# Qwiic_AHT20_Breakout.net
KiCad netlist of a schematic drawn in EAGLE
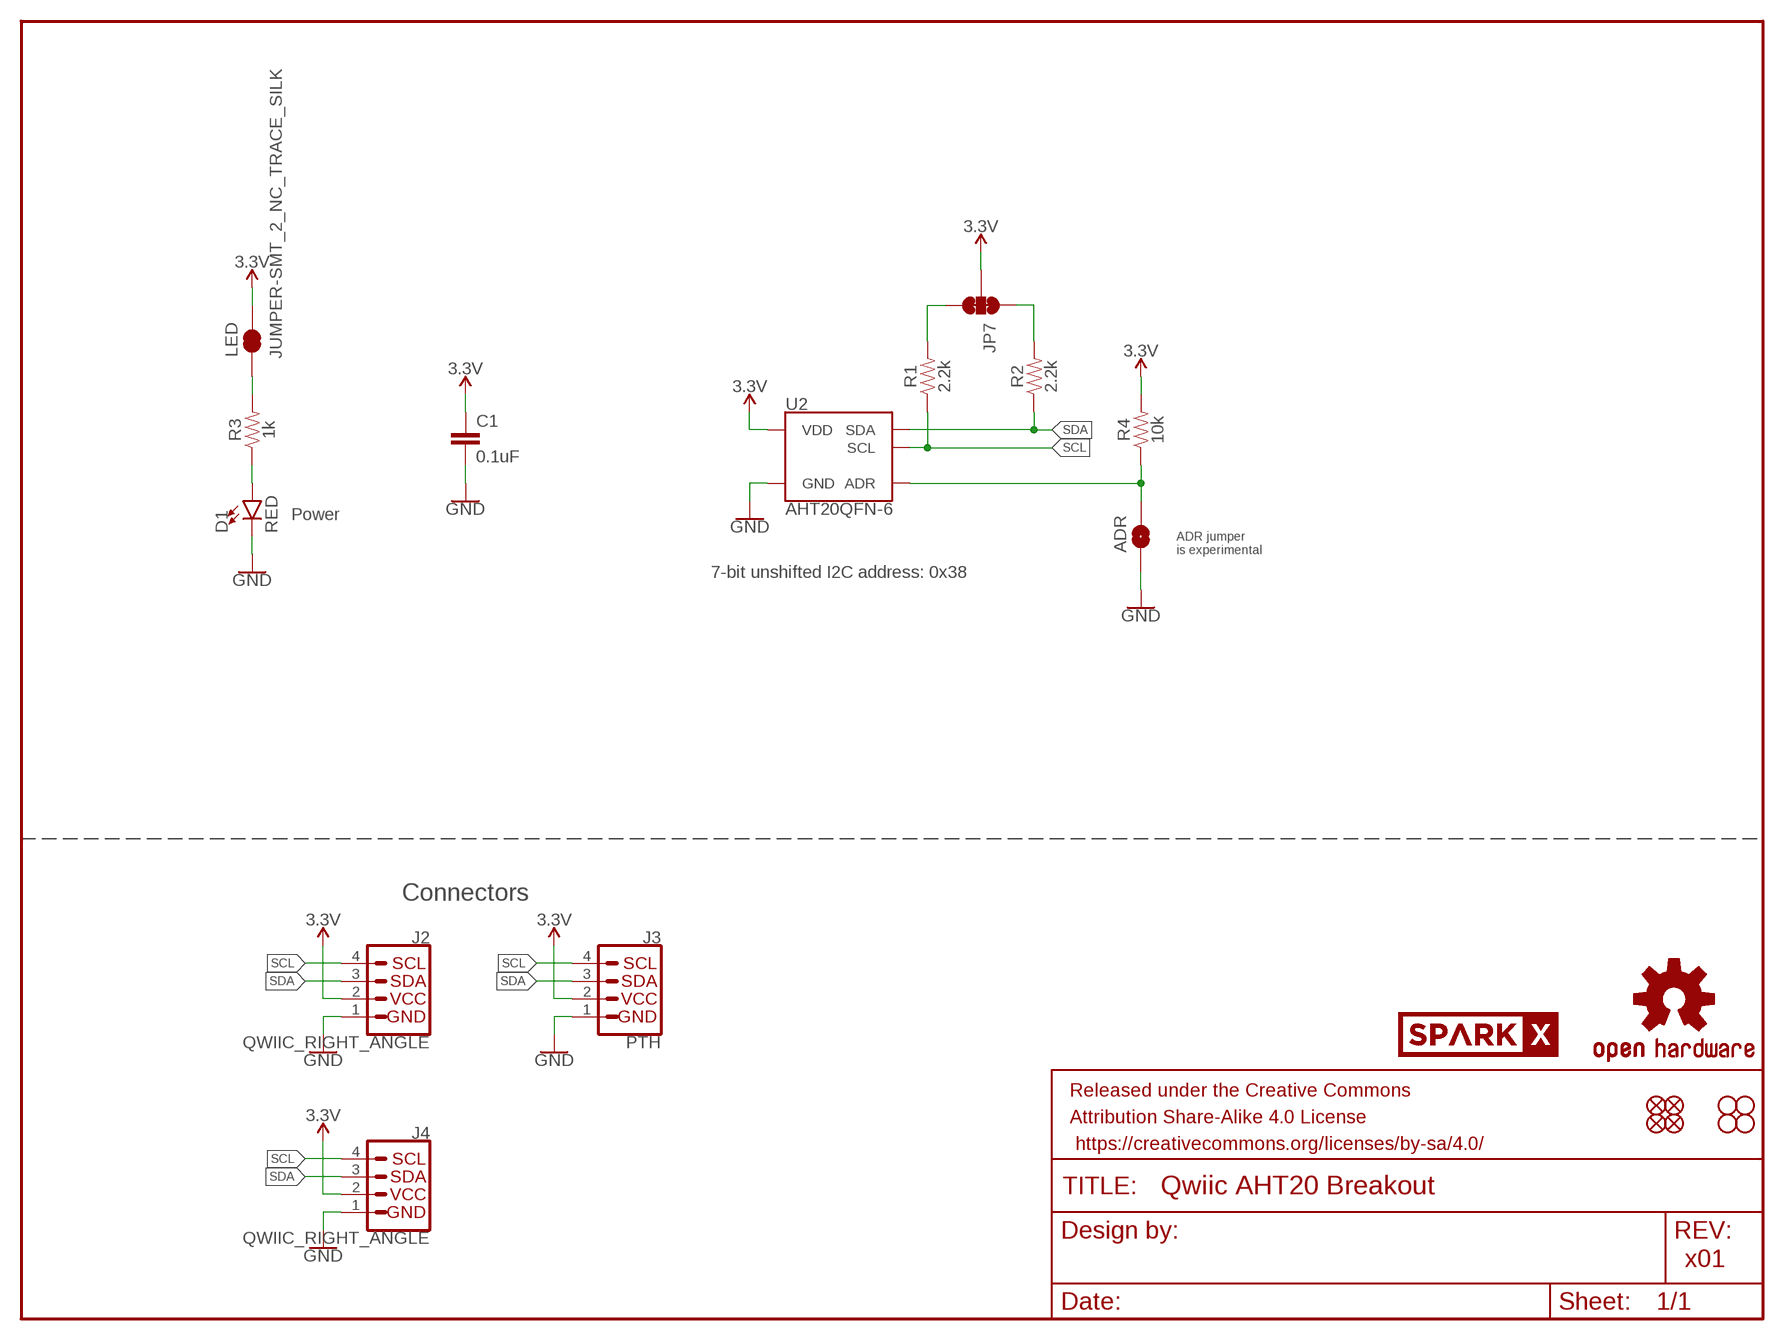
[diagram p0: schematic, sheet 1]

(export (version "E")
  (design (tool "Eeschema 10.0.6"))
  (components
    (comp (ref "ADR")
      (value "JUMPER-SMT_2_NO_SILK")
      (footprint "eagle-import:SMT-JUMPER_2_NO_SILK")
      (libsource (lib "eagle-import") (part "JUMPER-SMT_2_NO_SILK"))
    )
    (comp (ref "C1")
      (value "0.1uF")
      (footprint "eagle-import:0603")
      (libsource (lib "eagle-import") (part "0.1UF-0603-25V-(+80/-20%)"))
    )
    (comp (ref "D1")
      (value "RED")
      (footprint "eagle-import:LED-0603")
      (libsource (lib "eagle-import") (part "LED-RED0603"))
    )
    (comp (ref "FRAME1")
      (value "FRAME-LETTER")
      (footprint "eagle-import:CREATIVE_COMMONS")
      (libsource (lib "eagle-import") (part "FRAME-LETTER"))
    )
    (comp (ref "J2")
      (value "QWIIC_RIGHT_ANGLE")
      (footprint "eagle-import:JST04_1MM_RA")
      (libsource (lib "eagle-import") (part "QWIIC_CONNECTORJS-1MM"))
    )
    (comp (ref "J3")
      (value "PTH")
      (footprint "eagle-import:1X04_NO_SILK")
      (libsource (lib "eagle-import") (part "I2C_STANDARD_NO_SILK"))
    )
    (comp (ref "J4")
      (value "QWIIC_RIGHT_ANGLE")
      (footprint "eagle-import:JST04_1MM_RA")
      (libsource (lib "eagle-import") (part "QWIIC_CONNECTORJS-1MM"))
    )
    (comp (ref "JP1")
      (value "FIDUCIAL1X2")
      (footprint "eagle-import:FIDUCIAL-1X2")
      (libsource (lib "eagle-import") (part "FIDUCIAL1X2"))
    )
    (comp (ref "JP2")
      (value "FIDUCIAL1X2")
      (footprint "eagle-import:FIDUCIAL-1X2")
      (libsource (lib "eagle-import") (part "FIDUCIAL1X2"))
    )
    (comp (ref "JP3")
      (value "STAND-OFF")
      (footprint "eagle-import:STAND-OFF")
      (libsource (lib "eagle-import") (part "STAND-OFF"))
    )
    (comp (ref "JP4")
      (value "STAND-OFF")
      (footprint "eagle-import:STAND-OFF")
      (libsource (lib "eagle-import") (part "STAND-OFF"))
    )
    (comp (ref "JP5")
      (value "FIDUCIAL1X2")
      (footprint "eagle-import:FIDUCIAL-1X2")
      (libsource (lib "eagle-import") (part "FIDUCIAL1X2"))
    )
    (comp (ref "JP6")
      (value "FIDUCIAL1X2")
      (footprint "eagle-import:FIDUCIAL-1X2")
      (libsource (lib "eagle-import") (part "FIDUCIAL1X2"))
    )
    (comp (ref "JP7")
      (value "JUMPER-SMT_3_2-NC_TRACE_SILK")
      (footprint "eagle-import:SMT-JUMPER_3_2-NC_TRACE_SILK")
      (libsource (lib "eagle-import") (part "JUMPER-SMT_3_2-NC_TRACE_SILK"))
    )
    (comp (ref "JP8")
      (value "STAND-OFF")
      (footprint "eagle-import:STAND-OFF")
      (libsource (lib "eagle-import") (part "STAND-OFF"))
    )
    (comp (ref "JP9")
      (value "STAND-OFF")
      (footprint "eagle-import:STAND-OFF")
      (libsource (lib "eagle-import") (part "STAND-OFF"))
    )
    (comp (ref "LED")
      (value "JUMPER-SMT_2_NC_TRACE_SILK")
      (footprint "eagle-import:SMT-JUMPER_2_NC_TRACE_SILK")
      (libsource (lib "eagle-import") (part "JUMPER-SMT_2_NC_TRACE_SILK"))
    )
    (comp (ref "LOGO1")
      (value "OSHW-LOGOMINI")
      (footprint "eagle-import:OSHW-LOGO-MINI")
      (libsource (lib "eagle-import") (part "OSHW-LOGOMINI"))
    )
    (comp (ref "R1")
      (value "2.2k")
      (footprint "eagle-import:0603")
      (libsource (lib "eagle-import") (part "2.2KOHM-0603-1/10W-1%"))
    )
    (comp (ref "R2")
      (value "2.2k")
      (footprint "eagle-import:0603")
      (libsource (lib "eagle-import") (part "2.2KOHM-0603-1/10W-1%"))
    )
    (comp (ref "R3")
      (value "1k")
      (footprint "eagle-import:0603")
      (libsource (lib "eagle-import") (part "1KOHM-0603-1/10W-1%"))
    )
    (comp (ref "R4")
      (value "10k")
      (footprint "eagle-import:0603")
      (libsource (lib "eagle-import") (part "10KOHM-0603-1/10W-1%"))
    )
    (comp (ref "U$1")
      (value "SPARKX-LOGO4")
      (footprint "eagle-import:SPARKX-MEDIUM")
      (libsource (lib "eagle-import") (part "SPARKX-LOGO4"))
    )
    (comp (ref "U$2")
      (value "SPARKX-LOGO4")
      (footprint "eagle-import:SPARKX-MEDIUM")
      (libsource (lib "eagle-import") (part "SPARKX-LOGO4"))
    )
    (comp (ref "U2")
      (value "AHT20QFN-6")
      (footprint "eagle-import:QFN-6")
      (libsource (lib "eagle-import") (part "AHT20QFN-6"))
    )
  )
  (nets
    (net (code "1") (name "3.3V") (class "Default")
      (node (ref "C1") (pin "1") (pinfunction "1_1") (pintype "passive"))
      (node (ref "J2") (pin "2") (pinfunction "2_2") (pintype "power_in"))
      (node (ref "J3") (pin "2") (pinfunction "VCC_2") (pintype "power_in"))
      (node (ref "J4") (pin "2") (pinfunction "2_2") (pintype "power_in"))
      (node (ref "JP7") (pin "2") (pinfunction "2_2") (pintype "passive"))
      (node (ref "LED") (pin "2") (pinfunction "2_2") (pintype "passive"))
      (node (ref "R4") (pin "2") (pinfunction "2_2") (pintype "passive"))
      (node (ref "U2") (pin "VDD") (pinfunction "VDD_VDD") (pintype "power_in"))
    )
    (net (code "2") (name "GND") (class "Default")
      (node (ref "ADR") (pin "1") (pinfunction "1_1") (pintype "passive"))
      (node (ref "C1") (pin "2") (pinfunction "2_2") (pintype "passive"))
      (node (ref "D1") (pin "C") (pinfunction "C_C") (pintype "passive"))
      (node (ref "J2") (pin "1") (pinfunction "1_1") (pintype "power_in"))
      (node (ref "J3") (pin "1") (pinfunction "GND_1") (pintype "power_in"))
      (node (ref "J4") (pin "1") (pinfunction "1_1") (pintype "power_in"))
      (node (ref "U2") (pin "GND") (pinfunction "GND_GND") (pintype "power_in"))
    )
    (net (code "3") (name "Net-(ADR-Pad2)") (class "Default")
      (node (ref "ADR") (pin "2") (pinfunction "2_2") (pintype "passive"))
      (node (ref "R4") (pin "1") (pinfunction "1_1") (pintype "passive"))
      (node (ref "U2") (pin "ADR") (pinfunction "ADR_ADR") (pintype "input"))
    )
    (net (code "4") (name "Net-(D1-PadA)") (class "Default")
      (node (ref "D1") (pin "A") (pinfunction "A_A") (pintype "passive"))
      (node (ref "R3") (pin "1") (pinfunction "1_1") (pintype "passive"))
    )
    (net (code "5") (name "Net-(JP7-Pad1)") (class "Default")
      (node (ref "JP7") (pin "1") (pinfunction "1_1") (pintype "passive"))
      (node (ref "R2") (pin "2") (pinfunction "2_2") (pintype "passive"))
    )
    (net (code "6") (name "Net-(JP7-Pad3)") (class "Default")
      (node (ref "JP7") (pin "3") (pinfunction "3_3") (pintype "passive"))
      (node (ref "R1") (pin "2") (pinfunction "2_2") (pintype "passive"))
    )
    (net (code "7") (name "Net-(LED-Pad1)") (class "Default")
      (node (ref "LED") (pin "1") (pinfunction "1_1") (pintype "passive"))
      (node (ref "R3") (pin "2") (pinfunction "2_2") (pintype "passive"))
    )
    (net (code "8") (name "SCL") (class "Default")
      (node (ref "J2") (pin "4") (pinfunction "4_4") (pintype "passive"))
      (node (ref "J3") (pin "4") (pinfunction "SCL_4") (pintype "passive"))
      (node (ref "J4") (pin "4") (pinfunction "4_4") (pintype "passive"))
      (node (ref "R1") (pin "1") (pinfunction "1_1") (pintype "passive"))
      (node (ref "U2") (pin "SCL") (pinfunction "SCL_SCL") (pintype "input"))
    )
    (net (code "9") (name "SDA") (class "Default")
      (node (ref "J2") (pin "3") (pinfunction "3_3") (pintype "passive"))
      (node (ref "J3") (pin "3") (pinfunction "SDA_3") (pintype "passive"))
      (node (ref "J4") (pin "3") (pinfunction "3_3") (pintype "passive"))
      (node (ref "R2") (pin "1") (pinfunction "1_1") (pintype "passive"))
      (node (ref "U2") (pin "SDA") (pinfunction "SDA_SDA") (pintype "bidirectional"))
    )
  )
)
